# GiGaPower.net
KiCad netlist of a schematic drawn in EAGLE
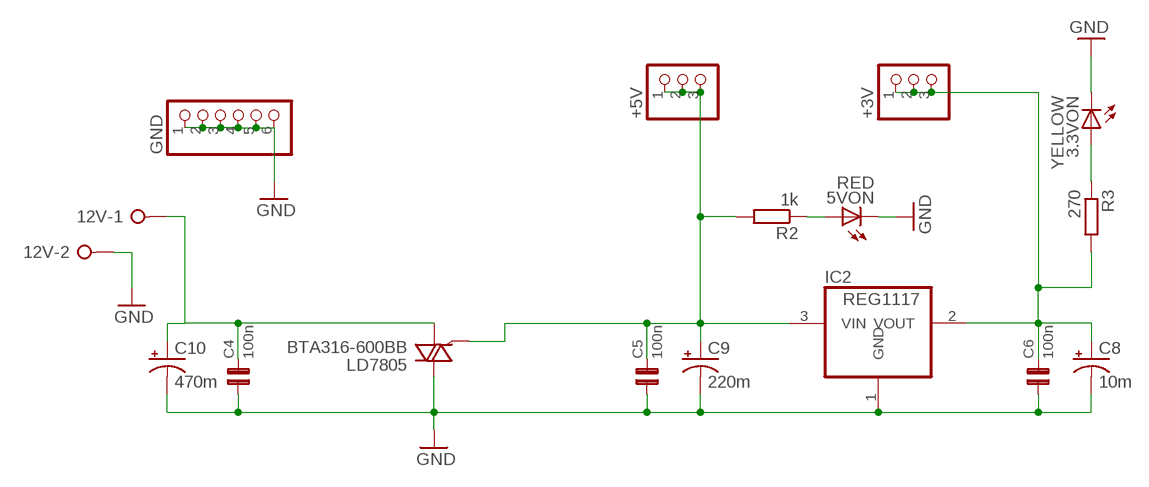
[diagram p0: schematic, sheet 1]

(export (version "E")
  (design (tool "Eeschema 10.0.6"))
  (components
    (comp (ref "+3V")
      (value "PINHD-1X3")
      (footprint "eagle-import:1X03")
      (libsource (lib "eagle-import") (part "PINHD-1X3"))
    )
    (comp (ref "+5V")
      (value "PINHD-1X3")
      (footprint "eagle-import:1X03")
      (libsource (lib "eagle-import") (part "PINHD-1X3"))
    )
    (comp (ref "3.3VON")
      (value "YELLOW")
      (footprint "eagle-import:CHIPLED_1206")
      (libsource (lib "eagle-import") (part "LEDCHIPLED_1206"))
    )
    (comp (ref "5VON")
      (value "RED")
      (footprint "eagle-import:CHIPLED_1206")
      (libsource (lib "eagle-import") (part "LEDCHIPLED_1206"))
    )
    (comp (ref "12V")
      (value "W237-02P")
      (footprint "eagle-import:W237-132")
      (libsource (lib "eagle-import") (part "W237-02P"))
    )
    (comp (ref "C4")
      (value "100n")
      (footprint "eagle-import:1206")
      (libsource (lib "eagle-import") (part "C1206"))
    )
    (comp (ref "C5")
      (value "100n")
      (footprint "eagle-import:1206")
      (libsource (lib "eagle-import") (part "C1206"))
    )
    (comp (ref "C6")
      (value "100n")
      (footprint "eagle-import:1206")
      (libsource (lib "eagle-import") (part "C1206"))
    )
    (comp (ref "C8")
      (value "10m")
      (footprint "eagle-import:UD-4X5,8_NICHICON")
      (libsource (lib "eagle-import") (part "CPOL-USUD-4X5,8"))
    )
    (comp (ref "C9")
      (value "220m")
      (footprint "eagle-import:UD-6,3X7,7_NICHICON")
      (libsource (lib "eagle-import") (part "CPOL-USUD-6,3X7,7"))
    )
    (comp (ref "C10")
      (value "470m")
      (footprint "eagle-import:UD-10X10_NICHICON")
      (libsource (lib "eagle-import") (part "CPOL-USUD-10X10"))
    )
    (comp (ref "GND")
      (value "PINHD-1X6")
      (footprint "eagle-import:1X06")
      (libsource (lib "eagle-import") (part "PINHD-1X6"))
    )
    (comp (ref "IC2")
      (value "REG1117")
      (footprint "eagle-import:SOT223")
      (libsource (lib "eagle-import") (part "REG1117"))
    )
    (comp (ref "LD7805")
      (value "BTA316-600BB")
      (footprint "eagle-import:SOT404")
      (libsource (lib "eagle-import") (part "BTA316B-600B"))
    )
    (comp (ref "R2")
      (value "1k")
      (footprint "eagle-import:R1206")
      (libsource (lib "eagle-import") (part "R-EU_R1206"))
    )
    (comp (ref "R3")
      (value "270")
      (footprint "eagle-import:R1206")
      (libsource (lib "eagle-import") (part "R-EU_R1206"))
    )
  )
  (nets
    (net (code "1") (name "GND") (class "Default")
      (node (ref "12V") (pin "2") (pinfunction "KL_2") (pintype "passive"))
      (node (ref "3.3VON") (pin "C") (pinfunction "C_C") (pintype "passive"))
      (node (ref "5VON") (pin "C") (pinfunction "C_C") (pintype "passive"))
      (node (ref "C10") (pin "-") (pinfunction "-_-") (pintype "passive"))
      (node (ref "C4") (pin "1") (pinfunction "1_1") (pintype "passive"))
      (node (ref "C5") (pin "1") (pinfunction "1_1") (pintype "passive"))
      (node (ref "C6") (pin "1") (pinfunction "1_1") (pintype "passive"))
      (node (ref "C8") (pin "-") (pinfunction "-_-") (pintype "passive"))
      (node (ref "C9") (pin "-") (pinfunction "-_-") (pintype "passive"))
      (node (ref "GND") (pin "1") (pinfunction "1_1") (pintype "passive"))
      (node (ref "GND") (pin "2") (pinfunction "2_2") (pintype "passive"))
      (node (ref "GND") (pin "3") (pinfunction "3_3") (pintype "passive"))
      (node (ref "GND") (pin "4") (pinfunction "4_4") (pintype "passive"))
      (node (ref "GND") (pin "5") (pinfunction "5_5") (pintype "passive"))
      (node (ref "GND") (pin "6") (pinfunction "6_6") (pintype "passive"))
      (node (ref "IC2") (pin "1") (pinfunction "GND_1") (pintype "power_in"))
      (node (ref "LD7805") (pin "MB") (pinfunction "LD_MB") (pintype "passive"))
    )
    (net (code "2") (name "Net-(3.3VON-PadA)") (class "Default")
      (node (ref "3.3VON") (pin "A") (pinfunction "A_A") (pintype "passive"))
      (node (ref "R3") (pin "1") (pinfunction "1_1") (pintype "passive"))
    )
    (net (code "3") (name "Net-(5VON-PadA)") (class "Default")
      (node (ref "5VON") (pin "A") (pinfunction "A_A") (pintype "passive"))
      (node (ref "R2") (pin "1") (pinfunction "1_1") (pintype "passive"))
    )
    (net (code "4") (name "Net-(12VA-KL)") (class "Default")
      (node (ref "12V") (pin "1") (pinfunction "KL_1") (pintype "passive"))
      (node (ref "C10") (pin "+") (pinfunction "+_+") (pintype "passive"))
      (node (ref "C4") (pin "2") (pinfunction "2_2") (pintype "passive"))
      (node (ref "LD7805") (pin "1") (pinfunction "CM_1") (pintype "passive"))
    )
    (net (code "5") (name "Net-(IC2-VIN)") (class "Default")
      (node (ref "+5V") (pin "1") (pinfunction "1_1") (pintype "passive"))
      (node (ref "+5V") (pin "2") (pinfunction "2_2") (pintype "passive"))
      (node (ref "+5V") (pin "3") (pinfunction "3_3") (pintype "passive"))
      (node (ref "C5") (pin "2") (pinfunction "2_2") (pintype "passive"))
      (node (ref "C9") (pin "+") (pinfunction "+_+") (pintype "passive"))
      (node (ref "IC2") (pin "3") (pinfunction "VIN_3") (pintype "input"))
      (node (ref "LD7805") (pin "3") (pinfunction "G_3") (pintype "passive"))
      (node (ref "R2") (pin "2") (pinfunction "2_2") (pintype "passive"))
    )
    (net (code "6") (name "Net-(IC2-VOUT)") (class "Default")
      (node (ref "+3V") (pin "1") (pinfunction "1_1") (pintype "passive"))
      (node (ref "+3V") (pin "2") (pinfunction "2_2") (pintype "passive"))
      (node (ref "+3V") (pin "3") (pinfunction "3_3") (pintype "passive"))
      (node (ref "C6") (pin "2") (pinfunction "2_2") (pintype "passive"))
      (node (ref "C8") (pin "+") (pinfunction "+_+") (pintype "passive"))
      (node (ref "IC2") (pin "2") (pinfunction "VOUT_2") (pintype "output"))
      (node (ref "R3") (pin "2") (pinfunction "2_2") (pintype "passive"))
    )
  )
)
